# megatari.net
KiCad netlist of a schematic drawn in EAGLE
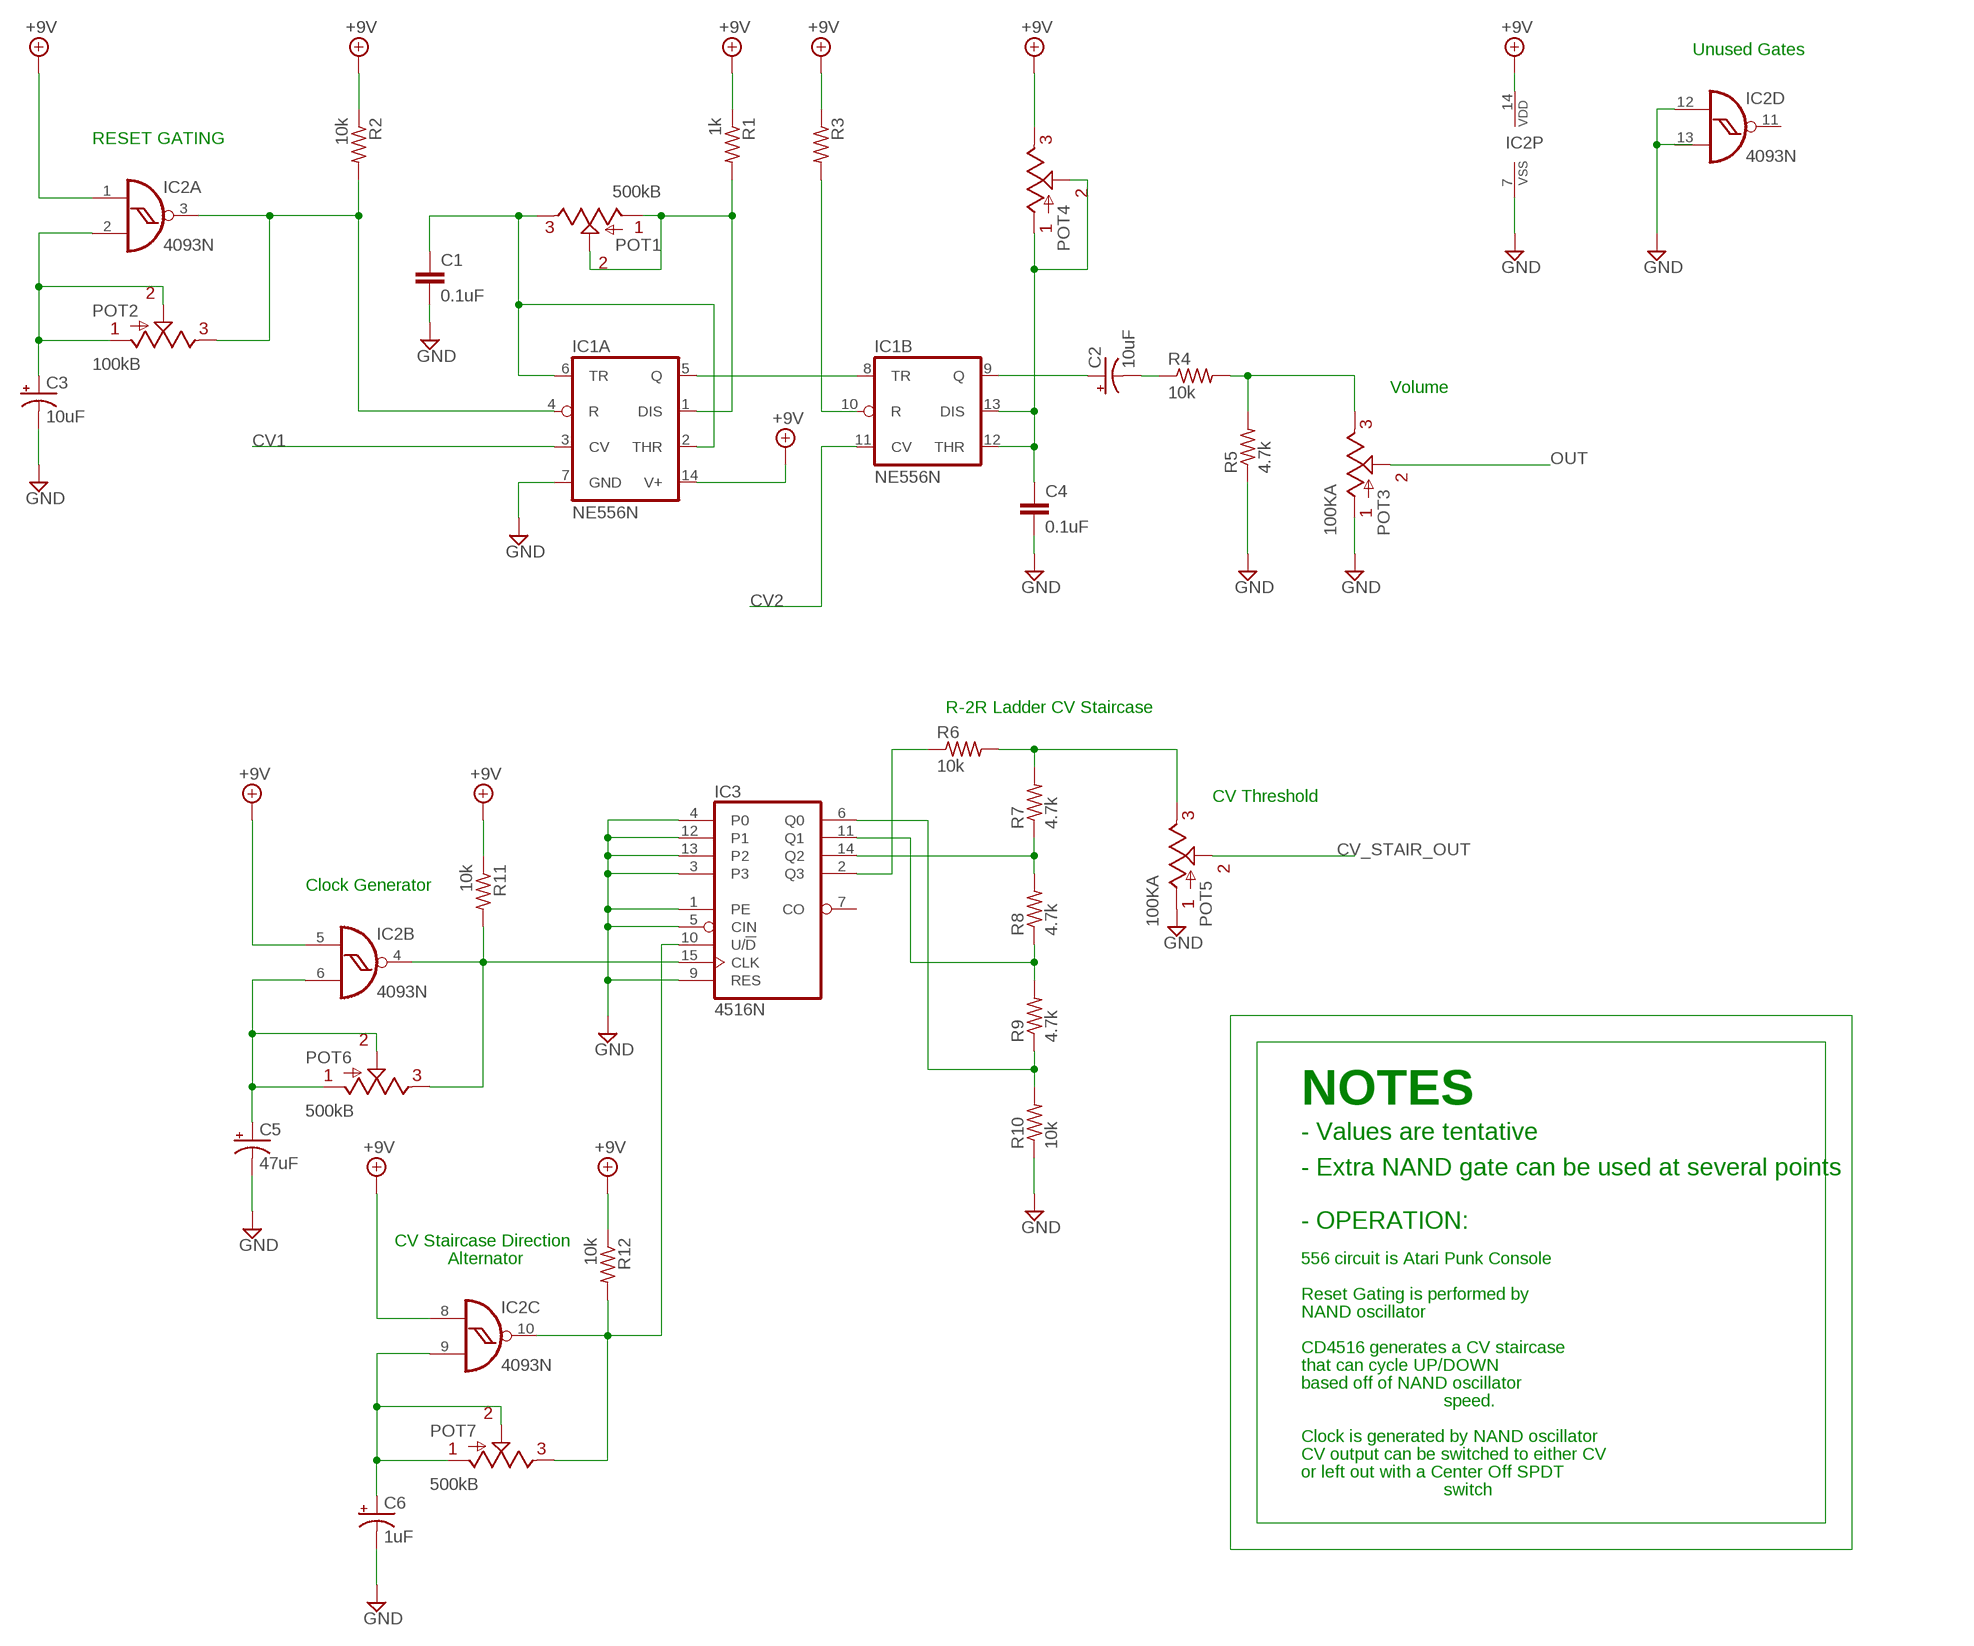
[diagram p0: schematic, sheet 1]

(export (version "E")
  (design (tool "Eeschema 10.0.6"))
  (components
    (comp (ref "C1")
      (value "0.1uF")
      (footprint "eagle-import:CERAMIC_CAP")
      (libsource (lib "eagle-import") (part "CERAMIC_CAPACITOR"))
    )
    (comp (ref "C2")
      (value "10uF")
      (footprint "eagle-import:050_020_1")
      (libsource (lib "eagle-import") (part "0501"))
    )
    (comp (ref "C3")
      (value "10uF")
      (footprint "eagle-import:050_020_1")
      (libsource (lib "eagle-import") (part "0501"))
    )
    (comp (ref "C4")
      (value "0.1uF")
      (footprint "eagle-import:CERAMIC_CAP")
      (libsource (lib "eagle-import") (part "CERAMIC_CAPACITOR"))
    )
    (comp (ref "C5")
      (value "47uF")
      (footprint "eagle-import:050_020_1")
      (libsource (lib "eagle-import") (part "0501"))
    )
    (comp (ref "C6")
      (value "1uF")
      (footprint "eagle-import:050_020_1")
      (libsource (lib "eagle-import") (part "0501"))
    )
    (comp (ref "IC1")
      (value "NE556N")
      (footprint "eagle-import:DIL14")
      (libsource (lib "eagle-import") (part "556NNE"))
    )
    (comp (ref "IC2")
      (value "4093N")
      (footprint "eagle-import:DIL14")
      (libsource (lib "eagle-import") (part "4093N"))
    )
    (comp (ref "IC3")
      (value "4516N")
      (footprint "eagle-import:DIL16")
      (libsource (lib "eagle-import") (part "4516N"))
    )
    (comp (ref "POT1")
      (value "500kB")
      (footprint "eagle-import:POT")
      (libsource (lib "eagle-import") (part "POT"))
    )
    (comp (ref "POT2")
      (value "100kB")
      (footprint "eagle-import:POT")
      (libsource (lib "eagle-import") (part "POT"))
    )
    (comp (ref "POT3")
      (value "100KA")
      (footprint "eagle-import:POT")
      (libsource (lib "eagle-import") (part "POT"))
    )
    (comp (ref "POT4")
      (value "POT")
      (footprint "eagle-import:POT")
      (libsource (lib "eagle-import") (part "POT"))
    )
    (comp (ref "POT5")
      (value "100KA")
      (footprint "eagle-import:POT")
      (libsource (lib "eagle-import") (part "POT"))
    )
    (comp (ref "POT6")
      (value "500kB")
      (footprint "eagle-import:POT")
      (libsource (lib "eagle-import") (part "POT"))
    )
    (comp (ref "POT7")
      (value "500kB")
      (footprint "eagle-import:POT")
      (libsource (lib "eagle-import") (part "POT"))
    )
    (comp (ref "R1")
      (value "1k")
      (footprint "eagle-import:RESISTOR")
      (libsource (lib "eagle-import") (part "RESISTOR"))
    )
    (comp (ref "R2")
      (value "10k")
      (footprint "eagle-import:RESISTOR")
      (libsource (lib "eagle-import") (part "RESISTOR"))
    )
    (comp (ref "R3")
      (value "RESISTOR")
      (footprint "eagle-import:RESISTOR")
      (libsource (lib "eagle-import") (part "RESISTOR"))
    )
    (comp (ref "R4")
      (value "10k")
      (footprint "eagle-import:RESISTOR")
      (libsource (lib "eagle-import") (part "RESISTOR"))
    )
    (comp (ref "R5")
      (value "4.7k")
      (footprint "eagle-import:RESISTOR")
      (libsource (lib "eagle-import") (part "RESISTOR"))
    )
    (comp (ref "R6")
      (value "10k")
      (footprint "eagle-import:RESISTOR")
      (libsource (lib "eagle-import") (part "RESISTOR"))
    )
    (comp (ref "R7")
      (value "4.7k")
      (footprint "eagle-import:RESISTOR")
      (libsource (lib "eagle-import") (part "RESISTOR"))
    )
    (comp (ref "R8")
      (value "4.7k")
      (footprint "eagle-import:RESISTOR")
      (libsource (lib "eagle-import") (part "RESISTOR"))
    )
    (comp (ref "R9")
      (value "4.7k")
      (footprint "eagle-import:RESISTOR")
      (libsource (lib "eagle-import") (part "RESISTOR"))
    )
    (comp (ref "R10")
      (value "10k")
      (footprint "eagle-import:RESISTOR")
      (libsource (lib "eagle-import") (part "RESISTOR"))
    )
    (comp (ref "R11")
      (value "10k")
      (footprint "eagle-import:RESISTOR")
      (libsource (lib "eagle-import") (part "RESISTOR"))
    )
    (comp (ref "R12")
      (value "10k")
      (footprint "eagle-import:RESISTOR")
      (libsource (lib "eagle-import") (part "RESISTOR"))
    )
  )
  (nets
    (net (code "1") (name "+9V") (class "Default")
      (node (ref "IC1") (pin "14") (pinfunction "V+_14") (pintype "power_in"))
      (node (ref "IC2") (pin "1") (pinfunction "I0_1") (pintype "input"))
      (node (ref "IC2") (pin "14") (pinfunction "VDD_14") (pintype "power_in"))
      (node (ref "IC2") (pin "5") (pinfunction "I0_5") (pintype "input"))
      (node (ref "IC2") (pin "8") (pinfunction "I0_8") (pintype "input"))
      (node (ref "POT4") (pin "3") (pinfunction "3_3") (pintype "passive"))
      (node (ref "R1") (pin "1") (pinfunction "1_1") (pintype "passive"))
      (node (ref "R11") (pin "1") (pinfunction "1_1") (pintype "passive"))
      (node (ref "R12") (pin "1") (pinfunction "1_1") (pintype "passive"))
      (node (ref "R2") (pin "1") (pinfunction "1_1") (pintype "passive"))
      (node (ref "R3") (pin "1") (pinfunction "1_1") (pintype "passive"))
    )
    (net (code "2") (name "/CV1") (class "Default")
      (node (ref "IC1") (pin "3") (pinfunction "CV_3") (pintype "input"))
    )
    (net (code "3") (name "/CV2") (class "Default")
      (node (ref "IC1") (pin "11") (pinfunction "CV_11") (pintype "input"))
    )
    (net (code "4") (name "/CV_STAIR_OUT") (class "Default")
      (node (ref "POT5") (pin "2") (pinfunction "2_2") (pintype "passive"))
    )
    (net (code "5") (name "/OUT") (class "Default")
      (node (ref "POT3") (pin "2") (pinfunction "2_2") (pintype "passive"))
    )
    (net (code "6") (name "GND") (class "Default")
      (node (ref "C1") (pin "2") (pinfunction "2_2") (pintype "passive"))
      (node (ref "C3") (pin "-") (pinfunction "-_-") (pintype "passive"))
      (node (ref "C4") (pin "2") (pinfunction "2_2") (pintype "passive"))
      (node (ref "C5") (pin "-") (pinfunction "-_-") (pintype "passive"))
      (node (ref "C6") (pin "-") (pinfunction "-_-") (pintype "passive"))
      (node (ref "IC1") (pin "7") (pinfunction "GND_7") (pintype "power_in"))
      (node (ref "IC2") (pin "12") (pinfunction "I0_12") (pintype "input"))
      (node (ref "IC2") (pin "7") (pinfunction "VSS_7") (pintype "power_in"))
      (node (ref "IC3") (pin "1") (pinfunction "PE_1") (pintype "input"))
      (node (ref "IC3") (pin "12") (pinfunction "P1_12") (pintype "input"))
      (node (ref "IC3") (pin "13") (pinfunction "P2_13") (pintype "input"))
      (node (ref "IC3") (pin "3") (pinfunction "P3_3") (pintype "input"))
      (node (ref "IC3") (pin "4") (pinfunction "P0_4") (pintype "input"))
      (node (ref "IC3") (pin "5") (pinfunction "CIN_5") (pintype "input"))
      (node (ref "IC3") (pin "9") (pinfunction "RES_9") (pintype "input"))
      (node (ref "POT3") (pin "1") (pinfunction "1_1") (pintype "passive"))
      (node (ref "POT5") (pin "1") (pinfunction "1_1") (pintype "passive"))
      (node (ref "R10") (pin "1") (pinfunction "1_1") (pintype "passive"))
      (node (ref "R5") (pin "1") (pinfunction "1_1") (pintype "passive"))
    )
    (net (code "7") (name "Net-(C2-Pad-)") (class "Default")
      (node (ref "C2") (pin "-") (pinfunction "-_-") (pintype "passive"))
      (node (ref "R4") (pin "1") (pinfunction "1_1") (pintype "passive"))
    )
    (net (code "8") (name "Net-(IC1A-DIS)") (class "Default")
      (node (ref "IC1") (pin "1") (pinfunction "DIS_1") (pintype "input"))
      (node (ref "POT1") (pin "1") (pinfunction "1_1") (pintype "passive"))
      (node (ref "POT1") (pin "2") (pinfunction "2_2") (pintype "passive"))
      (node (ref "R1") (pin "2") (pinfunction "2_2") (pintype "passive"))
    )
    (net (code "9") (name "Net-(IC1A-Q)") (class "Default")
      (node (ref "IC1") (pin "5") (pinfunction "Q_5") (pintype "output"))
      (node (ref "IC1") (pin "8") (pinfunction "TR_8") (pintype "input"))
    )
    (net (code "10") (name "Net-(IC1A-R)") (class "Default")
      (node (ref "IC1") (pin "4") (pinfunction "R_4") (pintype "input"))
      (node (ref "IC2") (pin "3") (pinfunction "O_3") (pintype "output"))
      (node (ref "POT2") (pin "3") (pinfunction "3_3") (pintype "passive"))
      (node (ref "R2") (pin "2") (pinfunction "2_2") (pintype "passive"))
    )
    (net (code "11") (name "Net-(IC1A-THR)") (class "Default")
      (node (ref "C1") (pin "1") (pinfunction "1_1") (pintype "passive"))
      (node (ref "IC1") (pin "2") (pinfunction "THR_2") (pintype "input"))
      (node (ref "IC1") (pin "6") (pinfunction "TR_6") (pintype "input"))
      (node (ref "POT1") (pin "3") (pinfunction "3_3") (pintype "passive"))
    )
    (net (code "12") (name "Net-(IC1B-DIS)") (class "Default")
      (node (ref "C4") (pin "1") (pinfunction "1_1") (pintype "passive"))
      (node (ref "IC1") (pin "12") (pinfunction "THR_12") (pintype "input"))
      (node (ref "IC1") (pin "13") (pinfunction "DIS_13") (pintype "input"))
      (node (ref "POT4") (pin "1") (pinfunction "1_1") (pintype "passive"))
      (node (ref "POT4") (pin "2") (pinfunction "2_2") (pintype "passive"))
    )
    (net (code "13") (name "Net-(IC1B-Q)") (class "Default")
      (node (ref "C2") (pin "+") (pinfunction "+_+") (pintype "passive"))
      (node (ref "IC1") (pin "9") (pinfunction "Q_9") (pintype "output"))
    )
    (net (code "14") (name "Net-(IC1B-R)") (class "Default")
      (node (ref "IC1") (pin "10") (pinfunction "R_10") (pintype "input"))
      (node (ref "R3") (pin "2") (pinfunction "2_2") (pintype "passive"))
    )
    (net (code "15") (name "Net-(IC2A-I1)") (class "Default")
      (node (ref "C3") (pin "+") (pinfunction "+_+") (pintype "passive"))
      (node (ref "IC2") (pin "2") (pinfunction "I1_2") (pintype "input"))
      (node (ref "POT2") (pin "1") (pinfunction "1_1") (pintype "passive"))
      (node (ref "POT2") (pin "2") (pinfunction "2_2") (pintype "passive"))
    )
    (net (code "16") (name "Net-(IC2B-I1)") (class "Default")
      (node (ref "C5") (pin "+") (pinfunction "+_+") (pintype "passive"))
      (node (ref "IC2") (pin "6") (pinfunction "I1_6") (pintype "input"))
      (node (ref "POT6") (pin "1") (pinfunction "1_1") (pintype "passive"))
      (node (ref "POT6") (pin "2") (pinfunction "2_2") (pintype "passive"))
    )
    (net (code "17") (name "Net-(IC2B-O)") (class "Default")
      (node (ref "IC2") (pin "4") (pinfunction "O_4") (pintype "output"))
      (node (ref "IC3") (pin "15") (pinfunction "CLK_15") (pintype "input"))
      (node (ref "POT6") (pin "3") (pinfunction "3_3") (pintype "passive"))
      (node (ref "R11") (pin "2") (pinfunction "2_2") (pintype "passive"))
    )
    (net (code "18") (name "Net-(IC2C-I1)") (class "Default")
      (node (ref "C6") (pin "+") (pinfunction "+_+") (pintype "passive"))
      (node (ref "IC2") (pin "9") (pinfunction "I1_9") (pintype "input"))
      (node (ref "POT7") (pin "1") (pinfunction "1_1") (pintype "passive"))
      (node (ref "POT7") (pin "2") (pinfunction "2_2") (pintype "passive"))
    )
    (net (code "19") (name "Net-(IC2C-O)") (class "Default")
      (node (ref "IC2") (pin "10") (pinfunction "O_10") (pintype "output"))
      (node (ref "IC3") (pin "10") (pinfunction "U/~{D}_10") (pintype "input"))
      (node (ref "POT7") (pin "3") (pinfunction "3_3") (pintype "passive"))
      (node (ref "R12") (pin "2") (pinfunction "2_2") (pintype "passive"))
    )
    (net (code "20") (name "Net-(IC3A-Q0)") (class "Default")
      (node (ref "IC3") (pin "6") (pinfunction "Q0_6") (pintype "output"))
      (node (ref "R10") (pin "2") (pinfunction "2_2") (pintype "passive"))
      (node (ref "R9") (pin "1") (pinfunction "1_1") (pintype "passive"))
    )
    (net (code "21") (name "Net-(IC3A-Q1)") (class "Default")
      (node (ref "IC3") (pin "11") (pinfunction "Q1_11") (pintype "output"))
      (node (ref "R8") (pin "1") (pinfunction "1_1") (pintype "passive"))
      (node (ref "R9") (pin "2") (pinfunction "2_2") (pintype "passive"))
    )
    (net (code "22") (name "Net-(IC3A-Q2)") (class "Default")
      (node (ref "IC3") (pin "14") (pinfunction "Q2_14") (pintype "output"))
      (node (ref "R7") (pin "1") (pinfunction "1_1") (pintype "passive"))
      (node (ref "R8") (pin "2") (pinfunction "2_2") (pintype "passive"))
    )
    (net (code "23") (name "Net-(IC3A-Q3)") (class "Default")
      (node (ref "IC3") (pin "2") (pinfunction "Q3_2") (pintype "output"))
      (node (ref "R6") (pin "1") (pinfunction "1_1") (pintype "passive"))
    )
    (net (code "24") (name "Net-(POT3-Pad3)") (class "Default")
      (node (ref "POT3") (pin "3") (pinfunction "3_3") (pintype "passive"))
      (node (ref "R4") (pin "2") (pinfunction "2_2") (pintype "passive"))
      (node (ref "R5") (pin "2") (pinfunction "2_2") (pintype "passive"))
    )
    (net (code "25") (name "Net-(POT5-Pad3)") (class "Default")
      (node (ref "POT5") (pin "3") (pinfunction "3_3") (pintype "passive"))
      (node (ref "R6") (pin "2") (pinfunction "2_2") (pintype "passive"))
      (node (ref "R7") (pin "2") (pinfunction "2_2") (pintype "passive"))
    )
    (net (code "26") (name "unconnected-(IC2D-I1-Pad13)") (class "Default")
      (node (ref "IC2") (pin "13") (pinfunction "I1_13") (pintype "input"))
    )
    (net (code "27") (name "unconnected-(IC2D-O-Pad11)") (class "Default")
      (node (ref "IC2") (pin "11") (pinfunction "O_11") (pintype "output"))
    )
    (net (code "28") (name "unconnected-(IC3A-CO-Pad7)") (class "Default")
      (node (ref "IC3") (pin "7") (pinfunction "CO_7") (pintype "output"))
    )
  )
)
